# Audio_Codec.net
KiCad netlist of a schematic drawn in Altium Designer
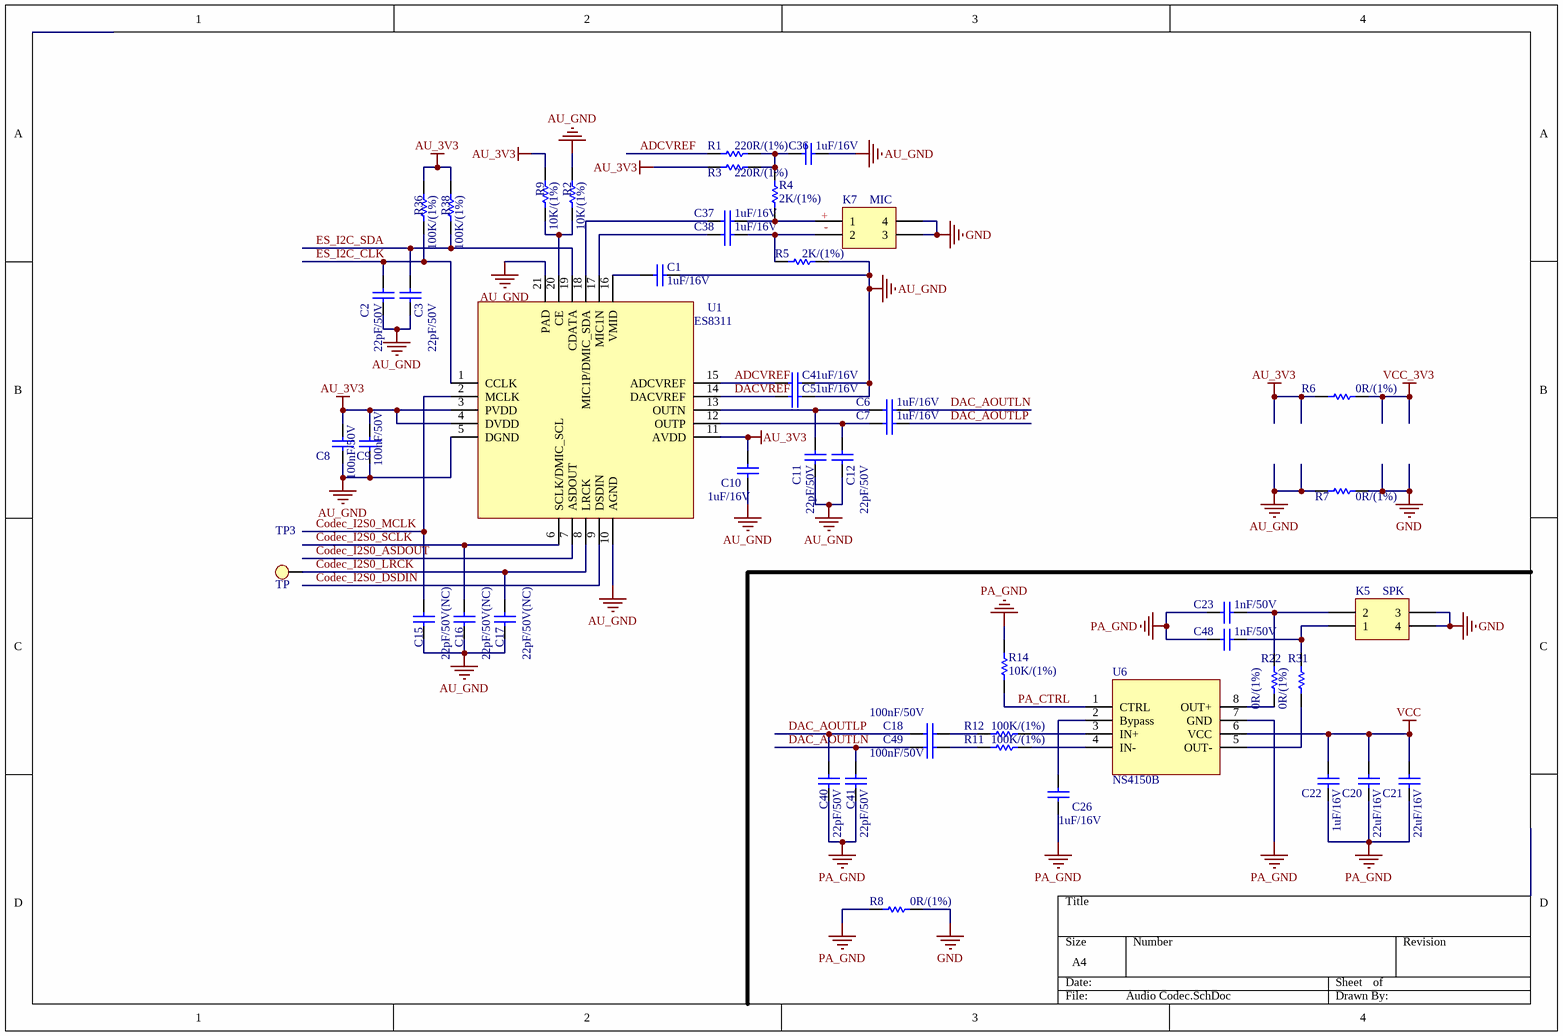
[diagram p0: Audio Codec.SchDoc]

(export (version "E")
  (design (tool "Eeschema 10.0.6"))
  (components
    (comp (ref "C1")
      (value "1uF/16V")
      (footprint "C0402")
      (description "Capacitor")
      (fields (field (name "PUBLISHER") "Altium Limited"))
      (libsource (lib "Miscellaneous Devices") (part "Cap"))
    )
    (comp (ref "C2")
      (value "22pF/50V")
      (footprint "C0402")
      (description "Capacitor")
      (fields (field (name "PUBLISHER") "Altium Limited"))
      (libsource (lib "Miscellaneous Devices") (part "Cap"))
    )
    (comp (ref "C3")
      (value "22pF/50V")
      (footprint "C0402")
      (description "Capacitor")
      (fields (field (name "PUBLISHER") "Altium Limited"))
      (libsource (lib "Miscellaneous Devices") (part "Cap"))
    )
    (comp (ref "C4")
      (value "1uF/16V")
      (footprint "C0402")
      (description "Capacitor")
      (fields (field (name "PUBLISHER") "Altium Limited"))
      (libsource (lib "Miscellaneous Devices") (part "Cap"))
    )
    (comp (ref "C5")
      (value "1uF/16V")
      (footprint "C0402")
      (description "Capacitor")
      (fields (field (name "PUBLISHER") "Altium Limited"))
      (libsource (lib "Miscellaneous Devices") (part "Cap"))
    )
    (comp (ref "C6")
      (value "1uF/16V")
      (footprint "C0402")
      (description "Capacitor")
      (fields (field (name "PUBLISHER") "Altium Limited"))
      (libsource (lib "Miscellaneous Devices") (part "Cap"))
    )
    (comp (ref "C7")
      (value "1uF/16V")
      (footprint "C0402")
      (description "Capacitor")
      (fields (field (name "PUBLISHER") "Altium Limited"))
      (libsource (lib "Miscellaneous Devices") (part "Cap"))
    )
    (comp (ref "C8")
      (value "100nF/50V")
      (footprint "C0402")
      (description "Capacitor")
      (fields (field (name "PUBLISHER") "Altium Limited"))
      (libsource (lib "Miscellaneous Devices") (part "Cap"))
    )
    (comp (ref "C9")
      (value "100nF/50V")
      (footprint "C0402")
      (description "Capacitor")
      (fields (field (name "PUBLISHER") "Altium Limited"))
      (libsource (lib "Miscellaneous Devices") (part "Cap"))
    )
    (comp (ref "C10")
      (value "1uF/16V")
      (footprint "C0402")
      (description "Capacitor")
      (fields (field (name "PUBLISHER") "Altium Limited"))
      (libsource (lib "Miscellaneous Devices") (part "Cap"))
    )
    (comp (ref "C11")
      (value "22pF/50V")
      (footprint "C0402")
      (description "Capacitor")
      (fields (field (name "PUBLISHER") "Altium Limited"))
      (libsource (lib "Miscellaneous Devices") (part "Cap"))
    )
    (comp (ref "C12")
      (value "22pF/50V")
      (footprint "C0402")
      (description "Capacitor")
      (fields (field (name "PUBLISHER") "Altium Limited"))
      (libsource (lib "Miscellaneous Devices") (part "Cap"))
    )
    (comp (ref "C15")
      (value "22pF/50V(NC)")
      (footprint "C0402")
      (description "Capacitor")
      (fields (field (name "PUBLISHER") "Altium Limited"))
      (libsource (lib "Miscellaneous Devices") (part "Cap"))
    )
    (comp (ref "C16")
      (value "22pF/50V(NC)")
      (footprint "C0402")
      (description "Capacitor")
      (fields (field (name "PUBLISHER") "Altium Limited"))
      (libsource (lib "Miscellaneous Devices") (part "Cap"))
    )
    (comp (ref "C17")
      (value "22pF/50V(NC)")
      (footprint "C0402")
      (description "Capacitor")
      (fields (field (name "PUBLISHER") "Altium Limited"))
      (libsource (lib "Miscellaneous Devices") (part "Cap"))
    )
    (comp (ref "C18")
      (value "100nF/50V")
      (footprint "C0402")
      (description "Capacitor")
      (fields (field (name "PUBLISHER") "Altium Limited"))
      (libsource (lib "Miscellaneous Devices") (part "Cap"))
    )
    (comp (ref "C20")
      (value "22uF/16V")
      (footprint "C0402")
      (description "Capacitor")
      (fields (field (name "PUBLISHER") "Altium Limited"))
      (libsource (lib "Miscellaneous Devices") (part "Cap"))
    )
    (comp (ref "C21")
      (value "22uF/16V")
      (footprint "C0402")
      (description "Capacitor")
      (fields (field (name "PUBLISHER") "Altium Limited"))
      (libsource (lib "Miscellaneous Devices") (part "Cap"))
    )
    (comp (ref "C22")
      (value "1uF/16V")
      (footprint "C0402")
      (description "Capacitor")
      (fields (field (name "PUBLISHER") "Altium Limited"))
      (libsource (lib "Miscellaneous Devices") (part "Cap"))
    )
    (comp (ref "C23")
      (value "1nF/50V")
      (footprint "C0402")
      (description "Capacitor")
      (fields (field (name "PUBLISHER") "Altium Limited"))
      (libsource (lib "Miscellaneous Devices") (part "Cap"))
    )
    (comp (ref "C26")
      (value "1uF/16V")
      (footprint "C0402")
      (description "Capacitor")
      (fields (field (name "PUBLISHER") "Altium Limited"))
      (libsource (lib "Miscellaneous Devices") (part "Cap"))
    )
    (comp (ref "C36")
      (value "1uF/16V")
      (footprint "C0402")
      (description "Capacitor")
      (fields (field (name "PUBLISHER") "Altium Limited"))
      (libsource (lib "Miscellaneous Devices") (part "Cap"))
    )
    (comp (ref "C37")
      (value "1uF/16V")
      (footprint "C0402")
      (description "Capacitor")
      (fields (field (name "PUBLISHER") "Altium Limited"))
      (libsource (lib "Miscellaneous Devices") (part "Cap"))
    )
    (comp (ref "C38")
      (value "1uF/16V")
      (footprint "C0402")
      (description "Capacitor")
      (fields (field (name "PUBLISHER") "Altium Limited"))
      (libsource (lib "Miscellaneous Devices") (part "Cap"))
    )
    (comp (ref "C40")
      (value "22pF/50V")
      (footprint "C0402")
      (description "Capacitor")
      (fields (field (name "PUBLISHER") "Altium Limited"))
      (libsource (lib "Miscellaneous Devices") (part "Cap"))
    )
    (comp (ref "C41")
      (value "22pF/50V")
      (footprint "C0402")
      (description "Capacitor")
      (fields (field (name "PUBLISHER") "Altium Limited"))
      (libsource (lib "Miscellaneous Devices") (part "Cap"))
    )
    (comp (ref "C48")
      (value "1nF/50V")
      (footprint "C0402")
      (description "Capacitor")
      (fields (field (name "PUBLISHER") "Altium Limited"))
      (libsource (lib "Miscellaneous Devices") (part "Cap"))
    )
    (comp (ref "C49")
      (value "100nF/50V")
      (footprint "C0402")
      (description "Capacitor")
      (fields (field (name "PUBLISHER") "Altium Limited"))
      (libsource (lib "Miscellaneous Devices") (part "Cap"))
    )
    (comp (ref "K5")
      (value "SPK")
      (footprint "HC-1.25-2PWT")
      (description "Header, 2-Pin, Dual row")
      (fields (field (name "PUBLISHER") "Altium Limited"))
      (libsource (lib "") (part "Header 2X2_1"))
    )
    (comp (ref "K7")
      (value "MIC")
      (footprint "HC-1.25-2PWT")
      (description "Header, 2-Pin, Dual row")
      (fields (field (name "PUBLISHER") "Altium Limited"))
      (libsource (lib "Miscellaneous Connectors") (part "Header 2X2"))
    )
    (comp (ref "R1")
      (value "220R/(1%)")
      (footprint "R0402")
      (description "Resistor")
      (fields (field (name "PUBLISHER") "Altium Limited"))
      (libsource (lib "Miscellaneous Devices") (part "Res1"))
    )
    (comp (ref "R2")
      (value "10K/(1%)")
      (footprint "R0402")
      (description "Resistor")
      (fields (field (name "PUBLISHER") "Altium Limited"))
      (libsource (lib "Miscellaneous Devices") (part "Res1"))
    )
    (comp (ref "R3")
      (value "220R/(1%)")
      (footprint "R0402")
      (description "Resistor")
      (fields (field (name "PUBLISHER") "Altium Limited"))
      (libsource (lib "Miscellaneous Devices") (part "Res1"))
    )
    (comp (ref "R4")
      (value "2K/(1%)")
      (footprint "R0402")
      (description "Resistor")
      (fields (field (name "PUBLISHER") "Altium Limited"))
      (libsource (lib "Miscellaneous Devices") (part "Res1"))
    )
    (comp (ref "R5")
      (value "2K/(1%)")
      (footprint "R0402")
      (description "Resistor")
      (fields (field (name "PUBLISHER") "Altium Limited"))
      (libsource (lib "Miscellaneous Devices") (part "Res1"))
    )
    (comp (ref "R6")
      (value "0R/(1%)")
      (footprint "R0402")
      (description "Resistor")
      (fields (field (name "PUBLISHER") "Altium Limited"))
      (libsource (lib "Miscellaneous Devices") (part "Res1"))
    )
    (comp (ref "R7")
      (value "0R/(1%)")
      (footprint "R0402")
      (description "Resistor")
      (fields (field (name "PUBLISHER") "Altium Limited"))
      (libsource (lib "Miscellaneous Devices") (part "Res1"))
    )
    (comp (ref "R8")
      (value "0R/(1%)")
      (footprint "R0402")
      (description "Resistor")
      (fields (field (name "PUBLISHER") "Altium Limited"))
      (libsource (lib "Miscellaneous Devices") (part "Res1"))
    )
    (comp (ref "R9")
      (value "10K/(1%)")
      (footprint "R0402")
      (description "Resistor")
      (fields (field (name "PUBLISHER") "Altium Limited"))
      (libsource (lib "Miscellaneous Devices") (part "Res1"))
    )
    (comp (ref "R11")
      (value "100K/(1%)")
      (footprint "R0402")
      (description "Resistor")
      (fields (field (name "PUBLISHER") "Altium Limited"))
      (libsource (lib "Miscellaneous Devices") (part "Res1"))
    )
    (comp (ref "R12")
      (value "100K/(1%)")
      (footprint "R0402")
      (description "Resistor")
      (fields (field (name "PUBLISHER") "Altium Limited"))
      (libsource (lib "Miscellaneous Devices") (part "Res1"))
    )
    (comp (ref "R14")
      (value "10K/(1%)")
      (footprint "R0402")
      (description "Resistor")
      (fields (field (name "PUBLISHER") "Altium Limited"))
      (libsource (lib "Miscellaneous Devices") (part "Res1"))
    )
    (comp (ref "R22")
      (value "0R/(1%)")
      (footprint "R0402")
      (description "Resistor")
      (fields (field (name "PUBLISHER") "Altium Limited"))
      (libsource (lib "Miscellaneous Devices") (part "Res1"))
    )
    (comp (ref "R31")
      (value "0R/(1%)")
      (footprint "R0402")
      (description "Resistor")
      (fields (field (name "PUBLISHER") "Altium Limited"))
      (libsource (lib "Miscellaneous Devices") (part "Res1"))
    )
    (comp (ref "R36")
      (value "100K/(1%)")
      (footprint "R0402")
      (description "Resistor")
      (fields (field (name "PUBLISHER") "Altium Limited"))
      (libsource (lib "Miscellaneous Devices") (part "Res1"))
    )
    (comp (ref "R38")
      (value "100K/(1%)")
      (footprint "R0402")
      (description "Resistor")
      (fields (field (name "PUBLISHER") "Altium Limited"))
      (libsource (lib "Miscellaneous Devices") (part "Res1"))
    )
    (comp (ref "TP3") (value "TP") (footprint "TEST_SMD") (libsource (lib "ESP32-S3") (part "TP")))
    (comp (ref "U1")
      (value "ES8311")
      (footprint "WQFN-20-EP(3x3)_ES8311")
      (libsource (lib "ESP32-S3") (part "ES8311"))
    )
    (comp (ref "U6")
      (value "NS4150B")
      (footprint "MSOP-8_L3.0-W3.0")
      (libsource (lib "聊天机器人") (part "NS4150"))
    )
  )
  (nets
    (net (code "1") (name "/ADCVREF") (class "Default")
      (node (ref "C4") (pin "1") (pinfunction "1_1") (pintype "passive"))
      (node (ref "R1") (pin "1") (pinfunction "1_1") (pintype "passive"))
      (node (ref "U1") (pin "15") (pinfunction "ADCVREF_15") (pintype "passive"))
    )
    (net (code "2") (name "/Codec_I2S0_ASDOUT") (class "Default")
      (node (ref "U1") (pin "7") (pinfunction "ASDOUT_7") (pintype "passive"))
    )
    (net (code "3") (name "/Codec_I2S0_DSDIN") (class "Default")
      (node (ref "U1") (pin "9") (pinfunction "DSDIN_9") (pintype "passive"))
    )
    (net (code "4") (name "/Codec_I2S0_LRCK") (class "Default")
      (node (ref "C17") (pin "2") (pinfunction "2_2") (pintype "passive"))
      (node (ref "TP3") (pin "1") (pinfunction "1_1") (pintype "passive"))
      (node (ref "U1") (pin "8") (pinfunction "LRCK_8") (pintype "passive"))
    )
    (net (code "5") (name "/Codec_I2S0_MCLK") (class "Default")
      (node (ref "C15") (pin "2") (pinfunction "2_2") (pintype "passive"))
      (node (ref "U1") (pin "2") (pinfunction "MCLK_2") (pintype "passive"))
    )
    (net (code "6") (name "/Codec_I2S0_SCLK") (class "Default")
      (node (ref "C16") (pin "2") (pinfunction "2_2") (pintype "passive"))
      (node (ref "U1") (pin "6") (pinfunction "SCLK/DMIC_SCL_6") (pintype "passive"))
    )
    (net (code "7") (name "/DACVREF") (class "Default")
      (node (ref "C5") (pin "1") (pinfunction "1_1") (pintype "passive"))
      (node (ref "U1") (pin "14") (pinfunction "DACVREF_14") (pintype "passive"))
    )
    (net (code "8") (name "/DAC_AOUTLN") (class "Default")
      (node (ref "C41") (pin "2") (pinfunction "2_2") (pintype "passive"))
      (node (ref "C49") (pin "2") (pinfunction "2_2") (pintype "passive"))
      (node (ref "C6") (pin "1") (pinfunction "1_1") (pintype "passive"))
    )
    (net (code "9") (name "/DAC_AOUTLP") (class "Default")
      (node (ref "C18") (pin "2") (pinfunction "2_2") (pintype "passive"))
      (node (ref "C40") (pin "2") (pinfunction "2_2") (pintype "passive"))
      (node (ref "C7") (pin "1") (pinfunction "1_1") (pintype "passive"))
    )
    (net (code "10") (name "/ES_I2C_CLK") (class "Default")
      (node (ref "C2") (pin "2") (pinfunction "2_2") (pintype "passive"))
      (node (ref "R36") (pin "2") (pinfunction "2_2") (pintype "passive"))
      (node (ref "U1") (pin "1") (pinfunction "CCLK_1") (pintype "passive"))
    )
    (net (code "11") (name "/ES_I2C_SDA") (class "Default")
      (node (ref "C3") (pin "2") (pinfunction "2_2") (pintype "passive"))
      (node (ref "R38") (pin "2") (pinfunction "2_2") (pintype "passive"))
      (node (ref "U1") (pin "19") (pinfunction "CDATA_19") (pintype "passive"))
    )
    (net (code "12") (name "/PA_CTRL") (class "Default")
      (node (ref "R14") (pin "1") (pinfunction "1_1") (pintype "passive"))
      (node (ref "U6") (pin "1") (pinfunction "CTRL_1") (pintype "passive"))
    )
    (net (code "13") (name "AU_3V3") (class "Default")
      (node (ref "C10") (pin "2") (pinfunction "2_2") (pintype "passive"))
      (node (ref "C8") (pin "2") (pinfunction "2_2") (pintype "passive"))
      (node (ref "C9") (pin "2") (pinfunction "2_2") (pintype "passive"))
      (node (ref "R3") (pin "1") (pinfunction "1_1") (pintype "passive"))
      (node (ref "R36") (pin "1") (pinfunction "1_1") (pintype "passive"))
      (node (ref "R38") (pin "1") (pinfunction "1_1") (pintype "passive"))
      (node (ref "R6") (pin "1") (pinfunction "1_1") (pintype "passive"))
      (node (ref "R9") (pin "2") (pinfunction "2_2") (pintype "passive"))
      (node (ref "U1") (pin "11") (pinfunction "AVDD_11") (pintype "passive"))
      (node (ref "U1") (pin "3") (pinfunction "PVDD_3") (pintype "passive"))
      (node (ref "U1") (pin "4") (pinfunction "DVDD_4") (pintype "passive"))
    )
    (net (code "14") (name "AU_GND") (class "Default")
      (node (ref "C1") (pin "2") (pinfunction "2_2") (pintype "passive"))
      (node (ref "C10") (pin "1") (pinfunction "1_1") (pintype "passive"))
      (node (ref "C11") (pin "1") (pinfunction "1_1") (pintype "passive"))
      (node (ref "C12") (pin "1") (pinfunction "1_1") (pintype "passive"))
      (node (ref "C15") (pin "1") (pinfunction "1_1") (pintype "passive"))
      (node (ref "C16") (pin "1") (pinfunction "1_1") (pintype "passive"))
      (node (ref "C17") (pin "1") (pinfunction "1_1") (pintype "passive"))
      (node (ref "C2") (pin "1") (pinfunction "1_1") (pintype "passive"))
      (node (ref "C3") (pin "1") (pinfunction "1_1") (pintype "passive"))
      (node (ref "C36") (pin "2") (pinfunction "2_2") (pintype "passive"))
      (node (ref "C4") (pin "2") (pinfunction "2_2") (pintype "passive"))
      (node (ref "C5") (pin "2") (pinfunction "2_2") (pintype "passive"))
      (node (ref "C8") (pin "1") (pinfunction "1_1") (pintype "passive"))
      (node (ref "C9") (pin "1") (pinfunction "1_1") (pintype "passive"))
      (node (ref "R2") (pin "2") (pinfunction "2_2") (pintype "passive"))
      (node (ref "R5") (pin "2") (pinfunction "2_2") (pintype "passive"))
      (node (ref "R7") (pin "1") (pinfunction "1_1") (pintype "passive"))
      (node (ref "U1") (pin "10") (pinfunction "AGND_10") (pintype "passive"))
      (node (ref "U1") (pin "21") (pinfunction "PAD_21") (pintype "passive"))
      (node (ref "U1") (pin "5") (pinfunction "DGND_5") (pintype "passive"))
    )
    (net (code "15") (name "GND") (class "Default")
      (node (ref "K5") (pin "3") (pinfunction "3_3") (pintype "passive"))
      (node (ref "K5") (pin "4") (pinfunction "4_4") (pintype "passive"))
      (node (ref "K7") (pin "3") (pinfunction "3_3") (pintype "passive"))
      (node (ref "K7") (pin "4") (pinfunction "4_4") (pintype "passive"))
      (node (ref "R7") (pin "2") (pinfunction "2_2") (pintype "passive"))
      (node (ref "R8") (pin "2") (pinfunction "2_2") (pintype "passive"))
    )
    (net (code "16") (name "Net-(C18-Pad1)") (class "Default")
      (node (ref "C18") (pin "1") (pinfunction "1_1") (pintype "passive"))
      (node (ref "R12") (pin "2") (pinfunction "2_2") (pintype "passive"))
    )
    (net (code "17") (name "Net-(C23-Pad1)") (class "Default")
      (node (ref "C23") (pin "1") (pinfunction "1_1") (pintype "passive"))
      (node (ref "K5") (pin "2") (pinfunction "2_2") (pintype "passive"))
      (node (ref "R22") (pin "2") (pinfunction "2_2") (pintype "passive"))
    )
    (net (code "18") (name "Net-(C36-Pad1)") (class "Default")
      (node (ref "C36") (pin "1") (pinfunction "1_1") (pintype "passive"))
      (node (ref "R1") (pin "2") (pinfunction "2_2") (pintype "passive"))
      (node (ref "R3") (pin "2") (pinfunction "2_2") (pintype "passive"))
      (node (ref "R4") (pin "1") (pinfunction "1_1") (pintype "passive"))
    )
    (net (code "19") (name "Net-(C37-Pad2)") (class "Default")
      (node (ref "C37") (pin "2") (pinfunction "2_2") (pintype "passive"))
      (node (ref "K7") (pin "1") (pinfunction "1_1") (pintype "passive"))
      (node (ref "R4") (pin "2") (pinfunction "2_2") (pintype "passive"))
    )
    (net (code "20") (name "Net-(C38-Pad2)") (class "Default")
      (node (ref "C38") (pin "2") (pinfunction "2_2") (pintype "passive"))
      (node (ref "K7") (pin "2") (pinfunction "2_2") (pintype "passive"))
      (node (ref "R5") (pin "1") (pinfunction "1_1") (pintype "passive"))
    )
    (net (code "21") (name "Net-(C48-Pad1)") (class "Default")
      (node (ref "C48") (pin "1") (pinfunction "1_1") (pintype "passive"))
      (node (ref "K5") (pin "1") (pinfunction "1_1") (pintype "passive"))
      (node (ref "R31") (pin "2") (pinfunction "2_2") (pintype "passive"))
    )
    (net (code "22") (name "Net-(C49-Pad1)") (class "Default")
      (node (ref "C49") (pin "1") (pinfunction "1_1") (pintype "passive"))
      (node (ref "R11") (pin "2") (pinfunction "2_2") (pintype "passive"))
    )
    (net (code "23") (name "Net-(U1-CE)") (class "Default")
      (node (ref "R2") (pin "1") (pinfunction "1_1") (pintype "passive"))
      (node (ref "R9") (pin "1") (pinfunction "1_1") (pintype "passive"))
      (node (ref "U1") (pin "20") (pinfunction "CE_20") (pintype "passive"))
    )
    (net (code "24") (name "Net-(U1-MIC1N)") (class "Default")
      (node (ref "C38") (pin "1") (pinfunction "1_1") (pintype "passive"))
      (node (ref "U1") (pin "17") (pinfunction "MIC1N_17") (pintype "passive"))
    )
    (net (code "25") (name "Net-(U1-MIC1P{slash}DMIC_SDA)") (class "Default")
      (node (ref "C37") (pin "1") (pinfunction "1_1") (pintype "passive"))
      (node (ref "U1") (pin "18") (pinfunction "MIC1P/DMIC_SDA_18") (pintype "passive"))
    )
    (net (code "26") (name "Net-(U1-OUTN)") (class "Default")
      (node (ref "C11") (pin "2") (pinfunction "2_2") (pintype "passive"))
      (node (ref "C6") (pin "2") (pinfunction "2_2") (pintype "passive"))
      (node (ref "U1") (pin "13") (pinfunction "OUTN_13") (pintype "passive"))
    )
    (net (code "27") (name "Net-(U1-OUTP)") (class "Default")
      (node (ref "C12") (pin "2") (pinfunction "2_2") (pintype "passive"))
      (node (ref "C7") (pin "2") (pinfunction "2_2") (pintype "passive"))
      (node (ref "U1") (pin "12") (pinfunction "OUTP_12") (pintype "passive"))
    )
    (net (code "28") (name "Net-(U1-VMID)") (class "Default")
      (node (ref "C1") (pin "1") (pinfunction "1_1") (pintype "passive"))
      (node (ref "U1") (pin "16") (pinfunction "VMID_16") (pintype "passive"))
    )
    (net (code "29") (name "Net-(U6-Bypass)") (class "Default")
      (node (ref "C26") (pin "1") (pinfunction "1_1") (pintype "passive"))
      (node (ref "U6") (pin "2") (pinfunction "Bypass_2") (pintype "passive"))
    )
    (net (code "30") (name "Net-(U6-IN+)") (class "Default")
      (node (ref "R12") (pin "1") (pinfunction "1_1") (pintype "passive"))
      (node (ref "U6") (pin "3") (pinfunction "IN+_3") (pintype "passive"))
    )
    (net (code "31") (name "Net-(U6-IN-)") (class "Default")
      (node (ref "R11") (pin "1") (pinfunction "1_1") (pintype "passive"))
      (node (ref "U6") (pin "4") (pinfunction "IN-_4") (pintype "passive"))
    )
    (net (code "32") (name "Net-(U6-OUT+)") (class "Default")
      (node (ref "R22") (pin "1") (pinfunction "1_1") (pintype "passive"))
      (node (ref "U6") (pin "8") (pinfunction "OUT+_8") (pintype "passive"))
    )
    (net (code "33") (name "Net-(U6-OUT-)") (class "Default")
      (node (ref "R31") (pin "1") (pinfunction "1_1") (pintype "passive"))
      (node (ref "U6") (pin "5") (pinfunction "OUT-_5") (pintype "passive"))
    )
    (net (code "34") (name "PA_GND") (class "Default")
      (node (ref "C20") (pin "1") (pinfunction "1_1") (pintype "passive"))
      (node (ref "C21") (pin "1") (pinfunction "1_1") (pintype "passive"))
      (node (ref "C22") (pin "1") (pinfunction "1_1") (pintype "passive"))
      (node (ref "C23") (pin "2") (pinfunction "2_2") (pintype "passive"))
      (node (ref "C26") (pin "2") (pinfunction "2_2") (pintype "passive"))
      (node (ref "C40") (pin "1") (pinfunction "1_1") (pintype "passive"))
      (node (ref "C41") (pin "1") (pinfunction "1_1") (pintype "passive"))
      (node (ref "C48") (pin "2") (pinfunction "2_2") (pintype "passive"))
      (node (ref "R14") (pin "2") (pinfunction "2_2") (pintype "passive"))
      (node (ref "R8") (pin "1") (pinfunction "1_1") (pintype "passive"))
      (node (ref "U6") (pin "7") (pinfunction "GND_7") (pintype "passive"))
    )
    (net (code "35") (name "VCC") (class "Default")
      (node (ref "C20") (pin "2") (pinfunction "2_2") (pintype "passive"))
      (node (ref "C21") (pin "2") (pinfunction "2_2") (pintype "passive"))
      (node (ref "C22") (pin "2") (pinfunction "2_2") (pintype "passive"))
      (node (ref "U6") (pin "6") (pinfunction "VCC_6") (pintype "passive"))
    )
    (net (code "36") (name "VCC_3V3") (class "Default")
      (node (ref "R6") (pin "2") (pinfunction "2_2") (pintype "passive"))
    )
  )
)
